# Raspberry_pi_connectors.net
KiCad netlist of a schematic drawn in Altium Designer
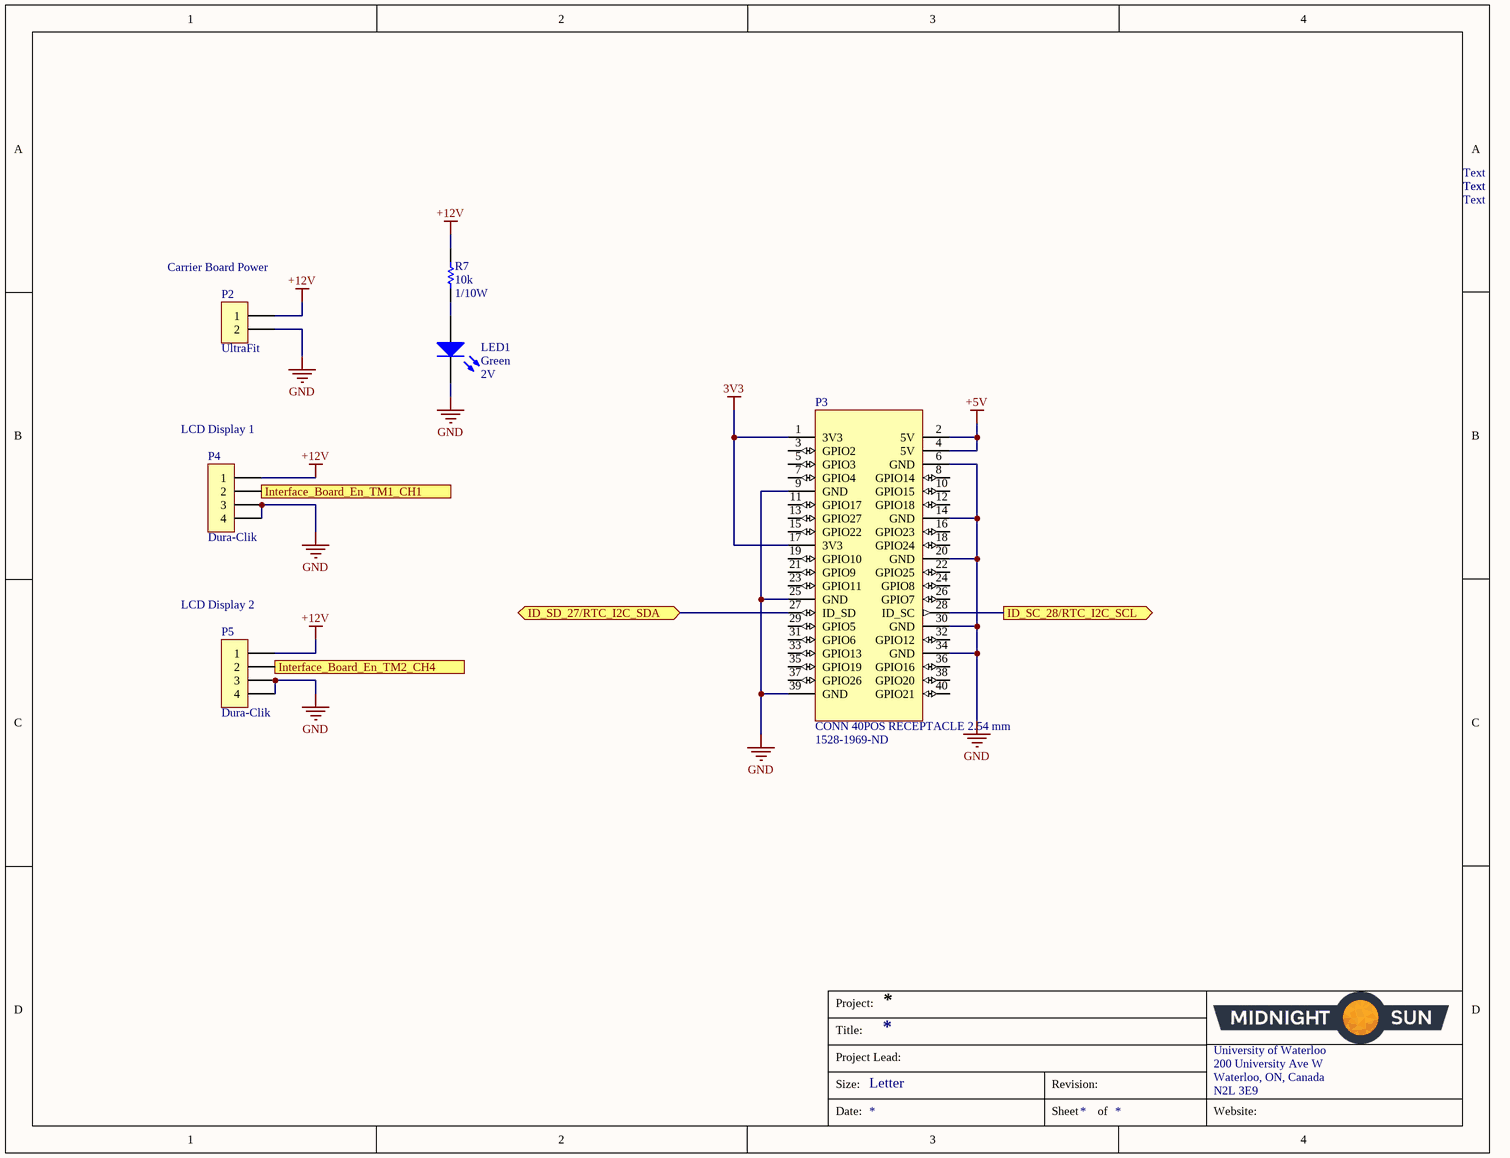
[diagram p0: Raspberry pi connectors.SchDoc]

(export (version "E")
  (design (tool "Eeschema 10.0.6"))
  (components
    (comp (ref "LED1")
      (value "LED GREEN CLEAR 2V 0603")
      (footprint "LED_0603")
      (description "Green 572nm LED Indication - Discrete 2V 0603 (1608 Metric)")
      (fields
        (field (name "MANUFACTURER") "Wurth Electronics Inc.")
        (field (name "MANUFACTURER PART NUMBER") "150060VS75000")
        (field (name "COLOR") "Green")
        (field (name "VOLTAGE - FORWARD (VF) (TYP)") "2V")
      )
      (libsource (lib "Schematic Diagrams") (part "LED GREEN CLEAR 2V 0603"))
    )
    (comp (ref "P2")
      (value "CONN 2POS ULTRA-FIT 0.138\"")
      (footprint "CONN, 2POS ULTRA-FIT")
      (description "2 Positions Header, Shrouded Connector 0.138\" (3.50mm) Through Hole Gold")
      (fields (field (name "VOLTAGE") "400V") (field (name "SERIES") "UltraFit"))
      (libsource (lib "Schematic Diagrams") (part "CONN 2POS ULTRA-FIT 0.138{dblquote}"))
    )
    (comp (ref "P3")
      (value "CONN 40POS RECEPTACLE 2.54 mm")
      (footprint "CONN 40POS RECEPTACLE 2.54 MM")
      (description "GPIO HEADER FOR RASPBERRYPI A+/B")
      (fields
        (field (name "MANUFACTURER") "Adafruit Industries")
        (field (name "MANUFACTURER PART NUMBER") "1992")
        (field (name "SUPPLIER PART NUMBER 1") "1528-1969-ND")
      )
      (libsource (lib "Schematic Diagrams") (part "CONN 40POS RECEPTACLE 2.54 mm"))
    )
    (comp (ref "P4")
      (value "Dura-Clik")
      (footprint "CONN, 4POS DURA-CLIK VERT")
      (description "4 Positions Header Connector 0.079\" (2.00mm) Surface Mount Tin")
      (fields
        (field (name "MANUFACTURER") "Molex, LLC")
        (field (name "MANUFACTURER PART NUMBER") "5600200420")
      )
      (libsource (lib "Schematic Diagrams") (part "CONN 4POS DURA-CLIK 0.079{dblquote}"))
    )
    (comp (ref "P5")
      (value "Dura-Clik")
      (footprint "CONN, 4POS DURA-CLIK VERT")
      (description "4 Positions Header Connector 0.079\" (2.00mm) Surface Mount Tin")
      (fields
        (field (name "MANUFACTURER") "Molex, LLC")
        (field (name "MANUFACTURER PART NUMBER") "5600200420")
      )
      (libsource (lib "Schematic Diagrams") (part "CONN 4POS DURA-CLIK 0.079{dblquote}"))
    )
    (comp (ref "R7")
      (value "RES 10K OHM 1% 1/10W 0603")
      (footprint "RES, 0603")
      (description "RES SMD 10K OHM 1% 1/10W 0603")
      (fields
        (field (name "TOLERANCE") "±1%")
        (field (name "RESISTANCE") "10k")
        (field (name "POWER") "1/10W")
      )
      (libsource (lib "Schematic Diagrams") (part "RES 10K OHM 1% 1/10W 0603"))
    )
  )
  (nets
    (net (code "1") (name "+5V") (class "Default")
      (node (ref "P3") (pin "2") (pinfunction "5V_2") (pintype "power_in"))
      (node (ref "P3") (pin "4") (pinfunction "5V_4") (pintype "power_in"))
    )
    (net (code "2") (name "+12V") (class "Default")
      (node (ref "P2") (pin "1") (pinfunction "1_1") (pintype "passive"))
      (node (ref "P4") (pin "1") (pinfunction "1_1") (pintype "passive"))
      (node (ref "P5") (pin "1") (pinfunction "1_1") (pintype "passive"))
      (node (ref "R7") (pin "2") (pinfunction "2_2") (pintype "passive"))
    )
    (net (code "3") (name "/ID_SC_28{slash}RTC_I2C_SCL") (class "Default")
      (node (ref "P3") (pin "28") (pinfunction "ID_SC_28") (pintype "output"))
    )
    (net (code "4") (name "/ID_SD_27{slash}RTC_I2C_SDA") (class "Default")
      (node (ref "P3") (pin "27") (pinfunction "ID_SD_27") (pintype "bidirectional"))
    )
    (net (code "5") (name "/Interface_Board_En_TM1_CH1") (class "Default")
      (node (ref "P4") (pin "2") (pinfunction "2_2") (pintype "passive"))
    )
    (net (code "6") (name "/Interface_Board_En_TM2_CH4") (class "Default")
      (node (ref "P5") (pin "2") (pinfunction "2_2") (pintype "passive"))
    )
    (net (code "7") (name "3V3") (class "Default")
      (node (ref "P3") (pin "1") (pinfunction "3V3_1") (pintype "power_in"))
      (node (ref "P3") (pin "17") (pinfunction "3V3_17") (pintype "power_in"))
    )
    (net (code "8") (name "GND") (class "Default")
      (node (ref "LED1") (pin "2") (pinfunction "K_2") (pintype "passive"))
      (node (ref "P2") (pin "2") (pinfunction "2_2") (pintype "passive"))
      (node (ref "P3") (pin "14") (pinfunction "GND_14") (pintype "power_in"))
      (node (ref "P3") (pin "20") (pinfunction "GND_20") (pintype "power_in"))
      (node (ref "P3") (pin "25") (pinfunction "GND_25") (pintype "power_in"))
      (node (ref "P3") (pin "30") (pinfunction "GND_30") (pintype "power_in"))
      (node (ref "P3") (pin "34") (pinfunction "GND_34") (pintype "power_in"))
      (node (ref "P3") (pin "39") (pinfunction "GND_39") (pintype "power_in"))
      (node (ref "P3") (pin "6") (pinfunction "GND_6") (pintype "power_in"))
      (node (ref "P3") (pin "9") (pinfunction "GND_9") (pintype "power_in"))
      (node (ref "P4") (pin "3") (pinfunction "3_3") (pintype "passive"))
      (node (ref "P4") (pin "4") (pinfunction "4_4") (pintype "passive"))
      (node (ref "P5") (pin "3") (pinfunction "3_3") (pintype "passive"))
      (node (ref "P5") (pin "4") (pinfunction "4_4") (pintype "passive"))
    )
    (net (code "9") (name "Net-(LED1-A)") (class "Default")
      (node (ref "LED1") (pin "1") (pinfunction "A_1") (pintype "passive"))
      (node (ref "R7") (pin "1") (pinfunction "1_1") (pintype "passive"))
    )
    (net (code "10") (name "unconnected-(P3-GPIO2-Pad3)") (class "Default")
      (node (ref "P3") (pin "3") (pinfunction "GPIO2_3") (pintype "bidirectional"))
    )
    (net (code "11") (name "unconnected-(P3-GPIO3-Pad5)") (class "Default")
      (node (ref "P3") (pin "5") (pinfunction "GPIO3_5") (pintype "bidirectional"))
    )
    (net (code "12") (name "unconnected-(P3-GPIO4-Pad7)") (class "Default")
      (node (ref "P3") (pin "7") (pinfunction "GPIO4_7") (pintype "bidirectional"))
    )
    (net (code "13") (name "unconnected-(P3-GPIO5-Pad29)") (class "Default")
      (node (ref "P3") (pin "29") (pinfunction "GPIO5_29") (pintype "bidirectional"))
    )
    (net (code "14") (name "unconnected-(P3-GPIO6-Pad31)") (class "Default")
      (node (ref "P3") (pin "31") (pinfunction "GPIO6_31") (pintype "bidirectional"))
    )
    (net (code "15") (name "unconnected-(P3-GPIO7-Pad26)") (class "Default")
      (node (ref "P3") (pin "26") (pinfunction "GPIO7_26") (pintype "bidirectional"))
    )
    (net (code "16") (name "unconnected-(P3-GPIO8-Pad24)") (class "Default")
      (node (ref "P3") (pin "24") (pinfunction "GPIO8_24") (pintype "bidirectional"))
    )
    (net (code "17") (name "unconnected-(P3-GPIO9-Pad21)") (class "Default")
      (node (ref "P3") (pin "21") (pinfunction "GPIO9_21") (pintype "bidirectional"))
    )
    (net (code "18") (name "unconnected-(P3-GPIO10-Pad19)") (class "Default")
      (node (ref "P3") (pin "19") (pinfunction "GPIO10_19") (pintype "bidirectional"))
    )
    (net (code "19") (name "unconnected-(P3-GPIO11-Pad23)") (class "Default")
      (node (ref "P3") (pin "23") (pinfunction "GPIO11_23") (pintype "bidirectional"))
    )
    (net (code "20") (name "unconnected-(P3-GPIO12-Pad32)") (class "Default")
      (node (ref "P3") (pin "32") (pinfunction "GPIO12_32") (pintype "bidirectional"))
    )
    (net (code "21") (name "unconnected-(P3-GPIO13-Pad33)") (class "Default")
      (node (ref "P3") (pin "33") (pinfunction "GPIO13_33") (pintype "bidirectional"))
    )
    (net (code "22") (name "unconnected-(P3-GPIO14-Pad8)") (class "Default")
      (node (ref "P3") (pin "8") (pinfunction "GPIO14_8") (pintype "bidirectional"))
    )
    (net (code "23") (name "unconnected-(P3-GPIO15-Pad10)") (class "Default")
      (node (ref "P3") (pin "10") (pinfunction "GPIO15_10") (pintype "bidirectional"))
    )
    (net (code "24") (name "unconnected-(P3-GPIO16-Pad36)") (class "Default")
      (node (ref "P3") (pin "36") (pinfunction "GPIO16_36") (pintype "bidirectional"))
    )
    (net (code "25") (name "unconnected-(P3-GPIO17-Pad11)") (class "Default")
      (node (ref "P3") (pin "11") (pinfunction "GPIO17_11") (pintype "bidirectional"))
    )
    (net (code "26") (name "unconnected-(P3-GPIO18-Pad12)") (class "Default")
      (node (ref "P3") (pin "12") (pinfunction "GPIO18_12") (pintype "bidirectional"))
    )
    (net (code "27") (name "unconnected-(P3-GPIO19-Pad35)") (class "Default")
      (node (ref "P3") (pin "35") (pinfunction "GPIO19_35") (pintype "bidirectional"))
    )
    (net (code "28") (name "unconnected-(P3-GPIO20-Pad38)") (class "Default")
      (node (ref "P3") (pin "38") (pinfunction "GPIO20_38") (pintype "bidirectional"))
    )
    (net (code "29") (name "unconnected-(P3-GPIO21-Pad40)") (class "Default")
      (node (ref "P3") (pin "40") (pinfunction "GPIO21_40") (pintype "bidirectional"))
    )
    (net (code "30") (name "unconnected-(P3-GPIO22-Pad15)") (class "Default")
      (node (ref "P3") (pin "15") (pinfunction "GPIO22_15") (pintype "bidirectional"))
    )
    (net (code "31") (name "unconnected-(P3-GPIO23-Pad16)") (class "Default")
      (node (ref "P3") (pin "16") (pinfunction "GPIO23_16") (pintype "bidirectional"))
    )
    (net (code "32") (name "unconnected-(P3-GPIO24-Pad18)") (class "Default")
      (node (ref "P3") (pin "18") (pinfunction "GPIO24_18") (pintype "bidirectional"))
    )
    (net (code "33") (name "unconnected-(P3-GPIO25-Pad22)") (class "Default")
      (node (ref "P3") (pin "22") (pinfunction "GPIO25_22") (pintype "bidirectional"))
    )
    (net (code "34") (name "unconnected-(P3-GPIO26-Pad37)") (class "Default")
      (node (ref "P3") (pin "37") (pinfunction "GPIO26_37") (pintype "bidirectional"))
    )
    (net (code "35") (name "unconnected-(P3-GPIO27-Pad13)") (class "Default")
      (node (ref "P3") (pin "13") (pinfunction "GPIO27_13") (pintype "bidirectional"))
    )
  )
)
